# Sheet1.net
KiCad netlist of a schematic drawn in Altium Designer
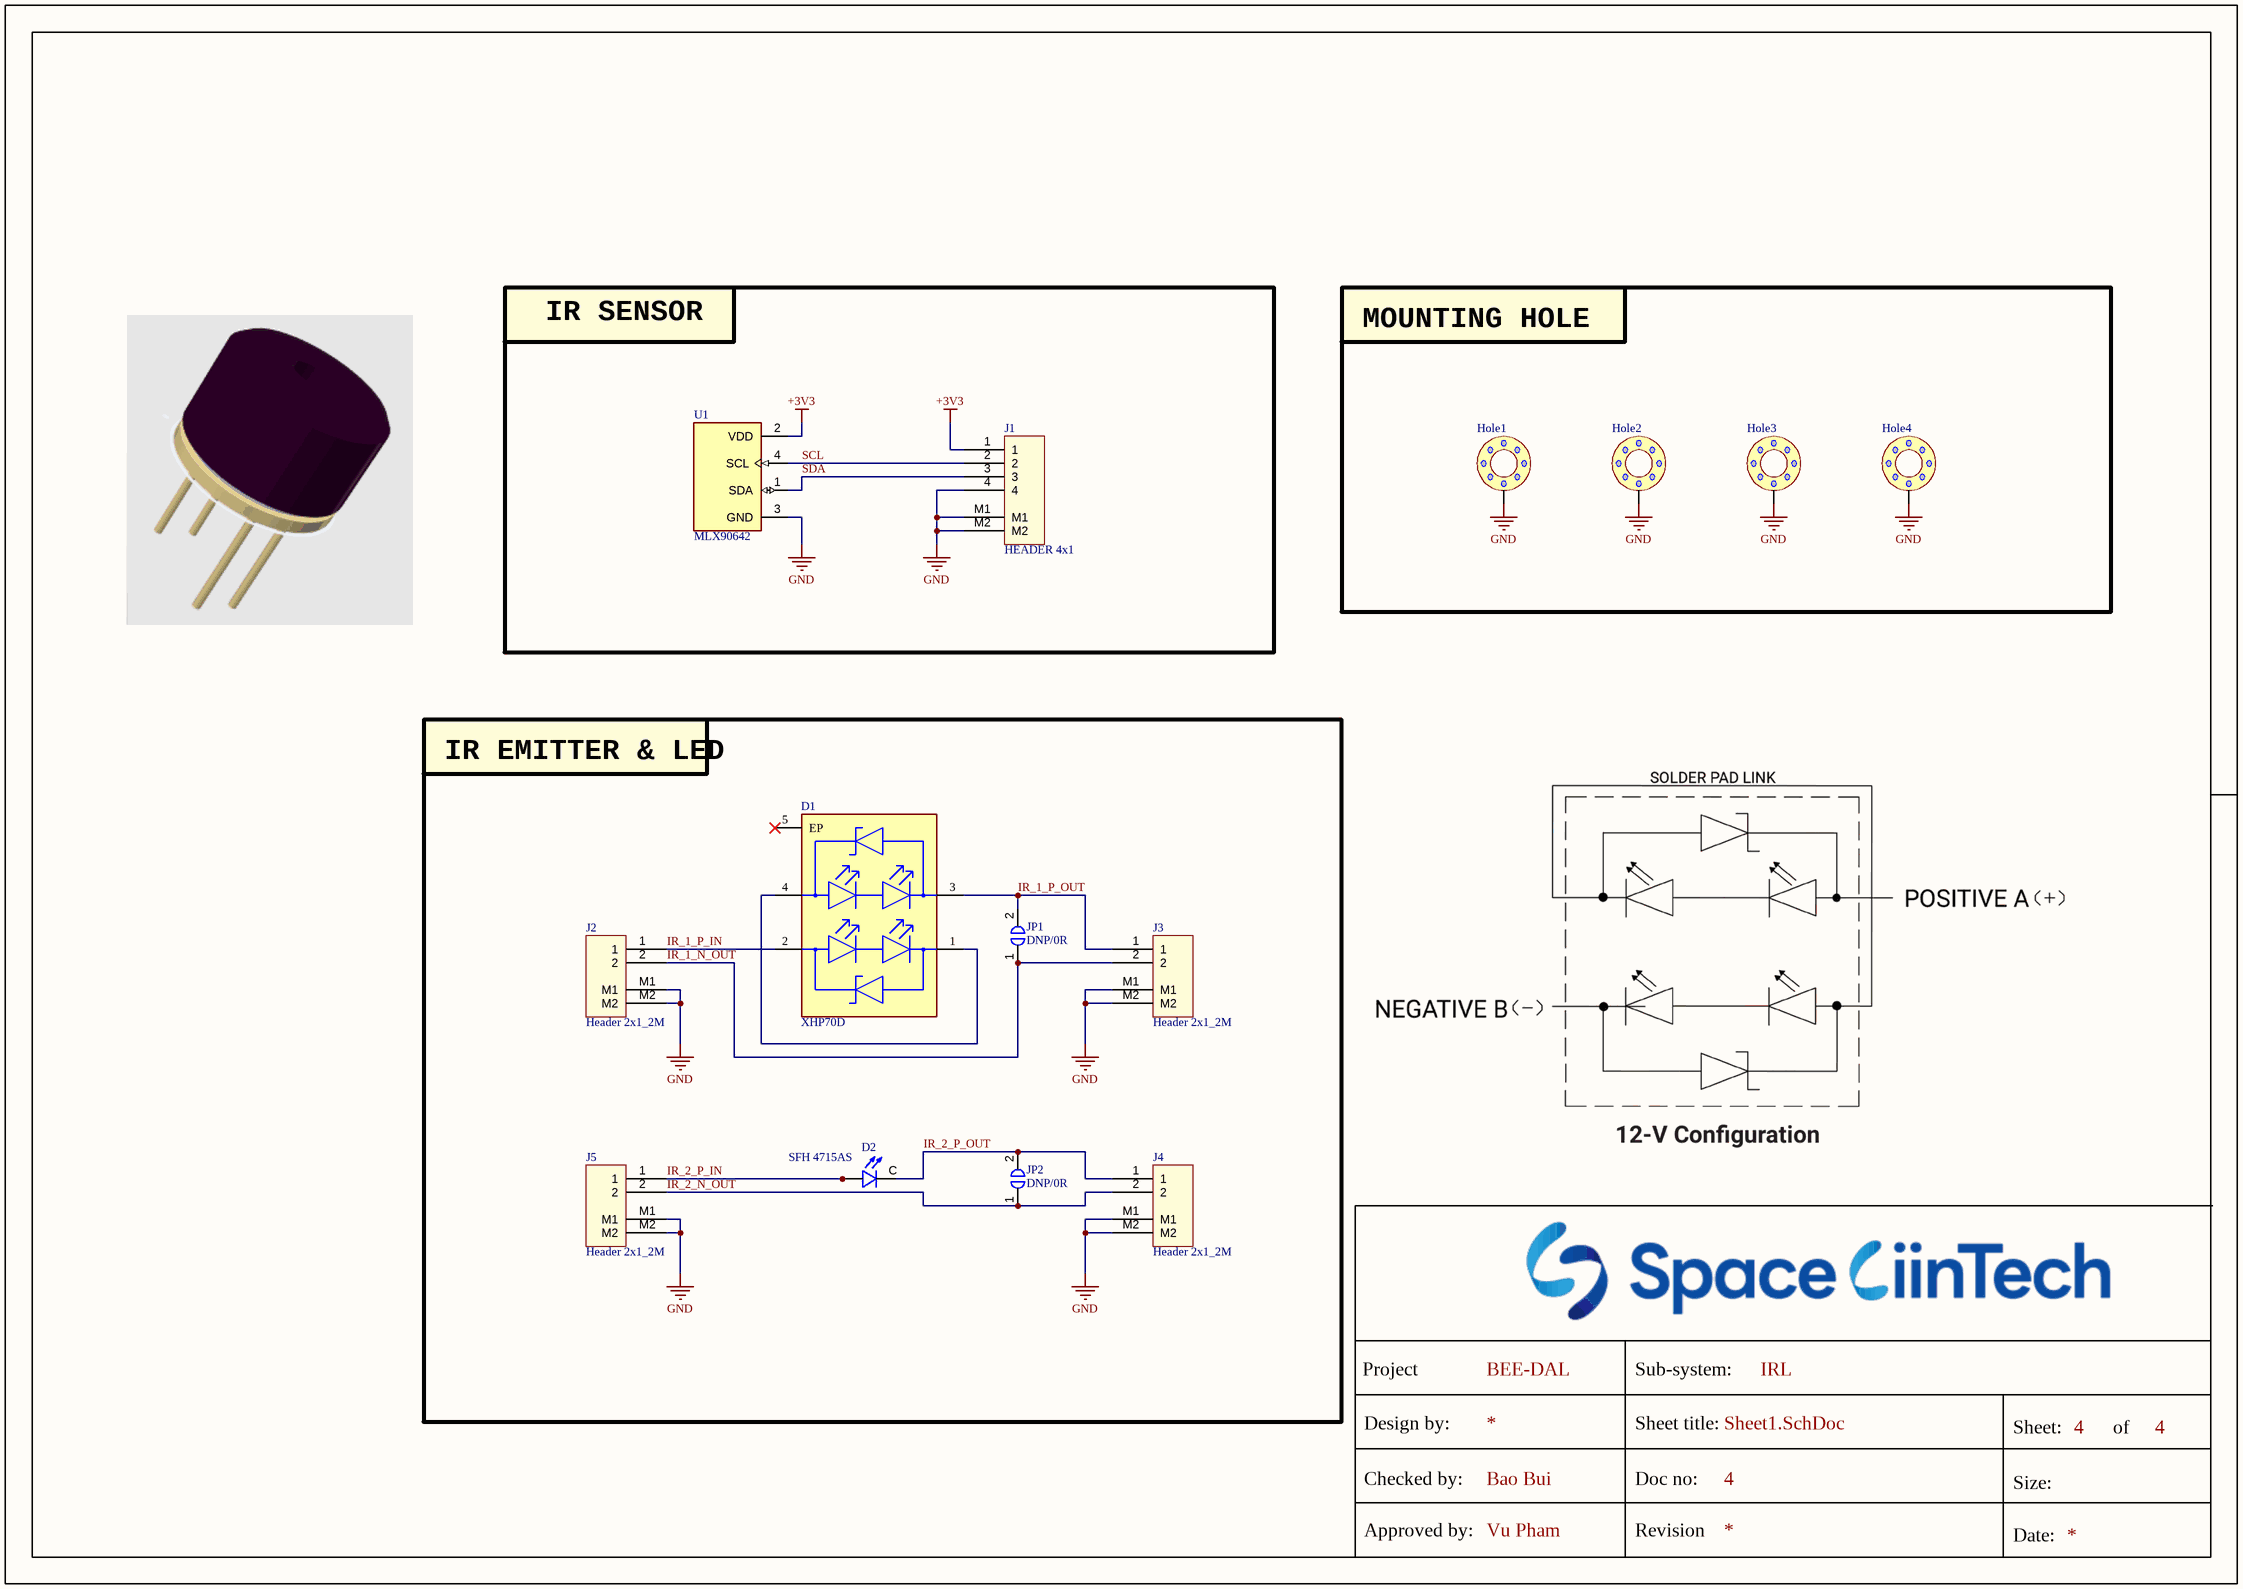
[diagram p0: Sheet1.SchDoc]

(export (version "E")
  (design (tool "Eeschema 10.0.6"))
  (components
    (comp (ref "D1")
      (value "XHP70D")
      (footprint "XHP70.3 High Intensity")
      (description "LED Lighting XLamp® XHP70.3 White, Cool 5000K 11.2V 1.05A 120° 2828")
      (libsource (lib "BEE_DAL_IRL") (part "XHP70D"))
    )
    (comp (ref "D2")
      (value "SFH 4715AS")
      (footprint "SFH 4715AS")
      (description "Infrared (IR) Emitter 860nm 3.2V 1.5A")
      (libsource (lib "BEE_DAL_IRL") (part "SFH 4715AS"))
    )
    (comp (ref "Hole1")
      (value "hole_space")
      (footprint "HEX-M3_NoVia")
      (libsource (lib "IFBschelib") (part "hole_space"))
    )
    (comp (ref "Hole2")
      (value "hole_space")
      (footprint "HEX-M3_NoVia")
      (libsource (lib "IFBschelib") (part "hole_space"))
    )
    (comp (ref "Hole3")
      (value "hole_space")
      (footprint "HEX-M3_NoVia")
      (libsource (lib "IFBschelib") (part "hole_space"))
    )
    (comp (ref "Hole4")
      (value "hole_space")
      (footprint "HEX-M3_NoVia")
      (libsource (lib "IFBschelib") (part "hole_space"))
    )
    (comp (ref "J1")
      (value "HEADER 4x1")
      (footprint "MOLEX_0532610471")
      (libsource (lib "LABLIB") (part "Header 4x1_2M"))
    )
    (comp (ref "J2")
      (value "Header 2x1_2M")
      (footprint "MOLEX_0532610271")
      (libsource (lib "") (part "Header 2x1_2M_1"))
    )
    (comp (ref "J3")
      (value "Header 2x1_2M")
      (footprint "MOLEX_0532610271")
      (libsource (lib "LABLIB") (part "Header 2x1_2M"))
    )
    (comp (ref "J4")
      (value "Header 2x1_2M")
      (footprint "MOLEX_0532610271")
      (libsource (lib "LABLIB") (part "Header 2x1_2M"))
    )
    (comp (ref "J5")
      (value "Header 2x1_2M")
      (footprint "MOLEX_0532610271")
      (libsource (lib "") (part "Header 2x1_2M_1"))
    )
    (comp (ref "JP1")
      (value "DNP/0R")
      (footprint "RES_C_1608X60")
      (libsource (lib "LABLIB") (part "JUMPER_1_1"))
    )
    (comp (ref "JP2")
      (value "DNP/0R")
      (footprint "RES_C_1608X60")
      (libsource (lib "LABLIB") (part "JUMPER_1_1"))
    )
    (comp (ref "U1")
      (value "MLX90642")
      (footprint "TO39 package")
      (description "32X24 THERMAL ARRAY, 110DEG FOV")
      (libsource (lib "BEE_DAL_IRL") (part "MLX90642"))
    )
  )
  (nets
    (net (code "1") (name "+3V3") (class "Default")
      (node (ref "J1") (pin "1") (pinfunction "1_1") (pintype "passive"))
      (node (ref "U1") (pin "2") (pinfunction "VDD_2") (pintype "power_in"))
    )
    (net (code "2") (name "/IR_1_N_OUT") (class "Default")
      (node (ref "J2") (pin "2") (pinfunction "2_2") (pintype "passive"))
      (node (ref "J3") (pin "2") (pinfunction "2_2") (pintype "passive"))
      (node (ref "JP1") (pin "1") (pinfunction "1_1") (pintype "passive"))
    )
    (net (code "3") (name "/IR_1_P_IN") (class "Default")
      (node (ref "D1") (pin "2") (pinfunction "1_ANODE_2") (pintype "passive"))
      (node (ref "J2") (pin "1") (pinfunction "1_1") (pintype "passive"))
    )
    (net (code "4") (name "/IR_1_P_OUT") (class "Default")
      (node (ref "D1") (pin "3") (pinfunction "2_CATHODE_3") (pintype "passive"))
      (node (ref "J3") (pin "1") (pinfunction "1_1") (pintype "passive"))
      (node (ref "JP1") (pin "2") (pinfunction "2_2") (pintype "passive"))
    )
    (net (code "5") (name "/IR_2_N_OUT") (class "Default")
      (node (ref "J4") (pin "2") (pinfunction "2_2") (pintype "passive"))
      (node (ref "J5") (pin "2") (pinfunction "2_2") (pintype "passive"))
      (node (ref "JP2") (pin "1") (pinfunction "1_1") (pintype "passive"))
    )
    (net (code "6") (name "/IR_2_P_IN") (class "Default")
      (node (ref "D2") (pin "A1") (pinfunction "A_A1") (pintype "passive"))
      (node (ref "D2") (pin "A2") (pinfunction "A_A2") (pintype "passive"))
      (node (ref "J5") (pin "1") (pinfunction "1_1") (pintype "passive"))
    )
    (net (code "7") (name "/IR_2_P_OUT") (class "Default")
      (node (ref "D2") (pin "C") (pinfunction "C_C") (pintype "passive"))
      (node (ref "J4") (pin "1") (pinfunction "1_1") (pintype "passive"))
      (node (ref "JP2") (pin "2") (pinfunction "2_2") (pintype "passive"))
    )
    (net (code "8") (name "/SCL") (class "Default")
      (node (ref "J1") (pin "2") (pinfunction "2_2") (pintype "passive"))
      (node (ref "U1") (pin "4") (pinfunction "SCL_4") (pintype "input"))
    )
    (net (code "9") (name "/SDA") (class "Default")
      (node (ref "J1") (pin "3") (pinfunction "3_3") (pintype "passive"))
      (node (ref "U1") (pin "1") (pinfunction "SDA_1") (pintype "bidirectional"))
    )
    (net (code "10") (name "GND") (class "Default")
      (node (ref "Hole1") (pin "1") (pinfunction "1_1") (pintype "passive"))
      (node (ref "Hole2") (pin "1") (pinfunction "1_1") (pintype "passive"))
      (node (ref "Hole3") (pin "1") (pinfunction "1_1") (pintype "passive"))
      (node (ref "Hole4") (pin "1") (pinfunction "1_1") (pintype "passive"))
      (node (ref "J1") (pin "4") (pinfunction "4_4") (pintype "passive"))
      (node (ref "J1") (pin "M1") (pinfunction "M1_M1") (pintype "passive"))
      (node (ref "J1") (pin "M2") (pinfunction "M2_M2") (pintype "passive"))
      (node (ref "J2") (pin "M1") (pinfunction "M1_M1") (pintype "passive"))
      (node (ref "J2") (pin "M2") (pinfunction "M2_M2") (pintype "passive"))
      (node (ref "J3") (pin "M1") (pinfunction "M1_M1") (pintype "passive"))
      (node (ref "J3") (pin "M2") (pinfunction "M2_M2") (pintype "passive"))
      (node (ref "J4") (pin "M1") (pinfunction "M1_M1") (pintype "passive"))
      (node (ref "J4") (pin "M2") (pinfunction "M2_M2") (pintype "passive"))
      (node (ref "J5") (pin "M1") (pinfunction "M1_M1") (pintype "passive"))
      (node (ref "J5") (pin "M2") (pinfunction "M2_M2") (pintype "passive"))
      (node (ref "U1") (pin "3") (pinfunction "GND_3") (pintype "power_in"))
    )
    (net (code "11") (name "Net-(D1-1_CATHODE)") (class "Default")
      (node (ref "D1") (pin "1") (pinfunction "1_CATHODE_1") (pintype "passive"))
      (node (ref "D1") (pin "4") (pinfunction "2_ANODE_4") (pintype "passive"))
    )
    (net (code "12") (name "unconnected-(D1-EP-Pad5)") (class "Default")
      (node (ref "D1") (pin "5") (pinfunction "EP_5") (pintype "passive+no_connect"))
    )
  )
)
